# LED_Ver_1.net
KiCad netlist of a schematic drawn in EAGLE
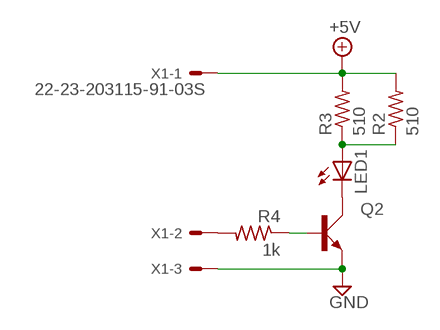
[diagram p0: schematic, sheet 1]

(export (version "E")
  (design (tool "Eeschema 10.0.6"))
  (components
    (comp (ref "LED1")
      (value "LED3528")
      (footprint "eagle-import:KA-3528ASYC")
      (libsource (lib "eagle-import") (part "LED3528"))
    )
    (comp (ref "Q2")
      (value "2SC2712")
      (footprint "eagle-import:SOT23")
      (libsource (lib "eagle-import") (part "2SC1815SOT"))
    )
    (comp (ref "R2")
      (value "510")
      (footprint "eagle-import:R1608")
      (libsource (lib "eagle-import") (part "R-US_R1608"))
    )
    (comp (ref "R3")
      (value "510")
      (footprint "eagle-import:R1608")
      (libsource (lib "eagle-import") (part "R-US_R1608"))
    )
    (comp (ref "R4")
      (value "1k")
      (footprint "eagle-import:R1608")
      (libsource (lib "eagle-import") (part "R-US_R1608"))
    )
    (comp (ref "X1")
      (value "22-23-203115-91-03S")
      (footprint "eagle-import:15-91-03S")
      (libsource (lib "eagle-import") (part "22-23-203115-91-03S"))
    )
  )
  (nets
    (net (code "1") (name "+5V") (class "Default")
      (node (ref "R2") (pin "2") (pinfunction "2_2") (pintype "passive"))
      (node (ref "R3") (pin "2") (pinfunction "2_2") (pintype "passive"))
      (node (ref "X1") (pin "1") (pinfunction "S_1") (pintype "passive"))
    )
    (net (code "2") (name "GND") (class "Default")
      (node (ref "Q2") (pin "2") (pinfunction "E_2") (pintype "passive"))
      (node (ref "X1") (pin "3") (pinfunction "S_3") (pintype "passive"))
    )
    (net (code "3") (name "Net-(LED1-PadA)") (class "Default")
      (node (ref "LED1") (pin "A") (pinfunction "A_A") (pintype "passive"))
      (node (ref "R2") (pin "1") (pinfunction "1_1") (pintype "passive"))
      (node (ref "R3") (pin "1") (pinfunction "1_1") (pintype "passive"))
    )
    (net (code "4") (name "Net-(Q2-B)") (class "Default")
      (node (ref "Q2") (pin "1") (pinfunction "B_1") (pintype "passive"))
      (node (ref "R4") (pin "1") (pinfunction "1_1") (pintype "passive"))
    )
    (net (code "5") (name "Net-(Q2-C)") (class "Default")
      (node (ref "LED1") (pin "C") (pinfunction "C_C") (pintype "passive"))
      (node (ref "Q2") (pin "3") (pinfunction "C_3") (pintype "passive"))
    )
    (net (code "6") (name "Net-(X1B-S)") (class "Default")
      (node (ref "R4") (pin "2") (pinfunction "2_2") (pintype "passive"))
      (node (ref "X1") (pin "2") (pinfunction "S_2") (pintype "passive"))
    )
  )
)
